# Resistive_Unequal_Power_Divider.net
KiCad netlist of a schematic drawn in Altium Designer
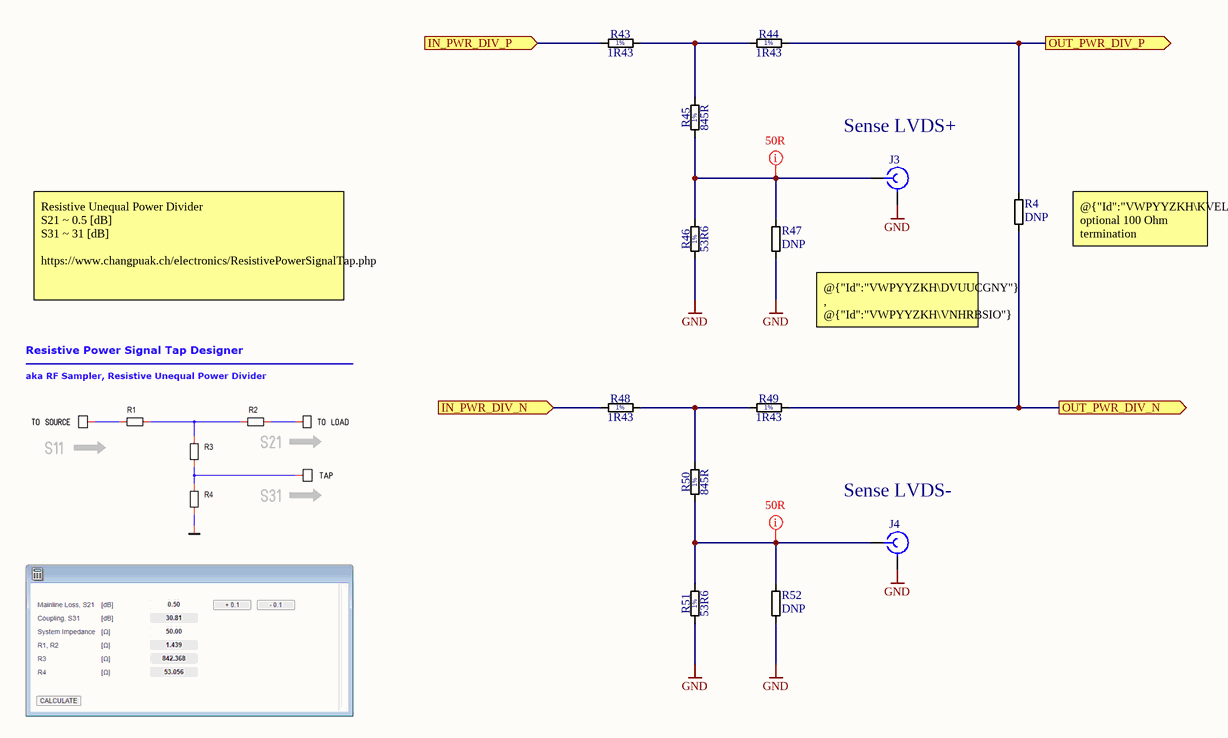
[diagram p0: Resistive_Unequal_Power_Divider.SchDoc]

(export (version "E")
  (design (tool "Eeschema 10.0.6"))
  (components
    (comp (ref "J3")
      (value "901-144-8RFX")
      (footprint "901-144-8RFX")
      (description "Coaxial Connectors VERTICAL PCB JACK GOLD PLATED BRASS")
      (libsource (lib "Connectors") (part "Coax_1Female_1Shield"))
    )
    (comp (ref "J4")
      (value "901-144-8RFX")
      (footprint "901-144-8RFX")
      (description "Coaxial Connectors VERTICAL PCB JACK GOLD PLATED BRASS")
      (libsource (lib "Connectors") (part "Coax_1Female_1Shield"))
    )
    (comp (ref "R4")
      (value "DNP")
      (footprint "RESC0402X40N")
      (description "General Purpose Thick Film Chip Resistor")
      (fields (field (name "VOLTAGE") "50V"))
      (libsource (lib "Resistors") (part "Resistor - Generic"))
    )
    (comp (ref "R43")
      (value "1R43")
      (footprint "RESC0402X40N")
      (description "General Purpose Thick Film Chip Resistor")
      (fields (field (name "MANUFACTURER PART NUMBER") "CRCW04021R43FKED") (field (name "TOLERANCE") "1%"))
      (libsource (lib "Resistors") (part "Resistor - 1%"))
    )
    (comp (ref "R44")
      (value "1R43")
      (footprint "RESC0402X40N")
      (description "General Purpose Thick Film Chip Resistor")
      (fields (field (name "MANUFACTURER PART NUMBER") "CRCW04021R43FKED") (field (name "TOLERANCE") "1%"))
      (libsource (lib "Resistors") (part "Resistor - 1%"))
    )
    (comp (ref "R45")
      (value "845R")
      (footprint "RESC0402X40N")
      (description "General Purpose Thick Film Chip Resistor")
      (fields (field (name "MANUFACTURER PART NUMBER") "RC0402FR-07845RL") (field (name "TOLERANCE") "1%"))
      (libsource (lib "Resistors") (part "Resistor - 1%"))
    )
    (comp (ref "R46")
      (value "53R6")
      (footprint "RESC0402X40N")
      (description "General Purpose Thick Film Chip Resistor")
      (fields (field (name "MANUFACTURER PART NUMBER") "RC0402FR-0753R6L") (field (name "TOLERANCE") "1%"))
      (libsource (lib "Resistors") (part "Resistor - 1%"))
    )
    (comp (ref "R47")
      (value "DNP")
      (footprint "RESC0402X40N")
      (description "General Purpose Thick Film Chip Resistor")
      (fields (field (name "VOLTAGE") "50V"))
      (libsource (lib "Resistors") (part "Resistor - Generic"))
    )
    (comp (ref "R48")
      (value "1R43")
      (footprint "RESC0402X40N")
      (description "General Purpose Thick Film Chip Resistor")
      (fields (field (name "MANUFACTURER PART NUMBER") "CRCW04021R43FKED") (field (name "TOLERANCE") "1%"))
      (libsource (lib "Resistors") (part "Resistor - 1%"))
    )
    (comp (ref "R49")
      (value "1R43")
      (footprint "RESC0402X40N")
      (description "General Purpose Thick Film Chip Resistor")
      (fields (field (name "MANUFACTURER PART NUMBER") "CRCW04021R43FKED") (field (name "TOLERANCE") "1%"))
      (libsource (lib "Resistors") (part "Resistor - 1%"))
    )
    (comp (ref "R50")
      (value "845R")
      (footprint "RESC0402X40N")
      (description "General Purpose Thick Film Chip Resistor")
      (fields (field (name "MANUFACTURER PART NUMBER") "RC0402FR-07845RL") (field (name "TOLERANCE") "1%"))
      (libsource (lib "Resistors") (part "Resistor - 1%"))
    )
    (comp (ref "R51")
      (value "53R6")
      (footprint "RESC0402X40N")
      (description "General Purpose Thick Film Chip Resistor")
      (fields (field (name "MANUFACTURER PART NUMBER") "RC0402FR-0753R6L") (field (name "TOLERANCE") "1%"))
      (libsource (lib "Resistors") (part "Resistor - 1%"))
    )
    (comp (ref "R52")
      (value "DNP")
      (footprint "RESC0402X40N")
      (description "General Purpose Thick Film Chip Resistor")
      (fields (field (name "VOLTAGE") "50V"))
      (libsource (lib "Resistors") (part "Resistor - Generic"))
    )
  )
  (nets
    (net (code "1") (name "/IN_PWR_DIV_N") (class "Default")
      (node (ref "R48") (pin "1") (pinfunction "1_1") (pintype "passive"))
    )
    (net (code "2") (name "/IN_PWR_DIV_P") (class "Default")
      (node (ref "R43") (pin "1") (pinfunction "1_1") (pintype "passive"))
    )
    (net (code "3") (name "/OUT_PWR_DIV_N") (class "Default")
      (node (ref "R4") (pin "1") (pinfunction "1_1") (pintype "passive"))
      (node (ref "R49") (pin "2") (pinfunction "2_2") (pintype "passive"))
    )
    (net (code "4") (name "/OUT_PWR_DIV_P") (class "Default")
      (node (ref "R4") (pin "2") (pinfunction "2_2") (pintype "passive"))
      (node (ref "R44") (pin "2") (pinfunction "2_2") (pintype "passive"))
    )
    (net (code "5") (name "GND") (class "Default")
      (node (ref "J3") (pin "2") (pinfunction "2_2") (pintype "passive"))
      (node (ref "J4") (pin "2") (pinfunction "2_2") (pintype "passive"))
      (node (ref "R46") (pin "1") (pinfunction "1_1") (pintype "passive"))
      (node (ref "R47") (pin "1") (pinfunction "1_1") (pintype "passive"))
      (node (ref "R51") (pin "1") (pinfunction "1_1") (pintype "passive"))
      (node (ref "R52") (pin "1") (pinfunction "1_1") (pintype "passive"))
    )
    (net (code "6") (name "Net-(J3-Pad1)") (class "Default")
      (node (ref "J3") (pin "1") (pinfunction "1_1") (pintype "passive"))
      (node (ref "R45") (pin "1") (pinfunction "1_1") (pintype "passive"))
      (node (ref "R46") (pin "2") (pinfunction "2_2") (pintype "passive"))
      (node (ref "R47") (pin "2") (pinfunction "2_2") (pintype "passive"))
    )
    (net (code "7") (name "Net-(J4-Pad1)") (class "Default")
      (node (ref "J4") (pin "1") (pinfunction "1_1") (pintype "passive"))
      (node (ref "R50") (pin "1") (pinfunction "1_1") (pintype "passive"))
      (node (ref "R51") (pin "2") (pinfunction "2_2") (pintype "passive"))
      (node (ref "R52") (pin "2") (pinfunction "2_2") (pintype "passive"))
    )
    (net (code "8") (name "Net-(R43-Pad2)") (class "Default")
      (node (ref "R43") (pin "2") (pinfunction "2_2") (pintype "passive"))
      (node (ref "R44") (pin "1") (pinfunction "1_1") (pintype "passive"))
      (node (ref "R45") (pin "2") (pinfunction "2_2") (pintype "passive"))
    )
    (net (code "9") (name "Net-(R48-Pad2)") (class "Default")
      (node (ref "R48") (pin "2") (pinfunction "2_2") (pintype "passive"))
      (node (ref "R49") (pin "1") (pinfunction "1_1") (pintype "passive"))
      (node (ref "R50") (pin "2") (pinfunction "2_2") (pintype "passive"))
    )
  )
)
